# nrf_ha_sensor_USB.net
KiCad netlist of a schematic drawn in Altium Designer
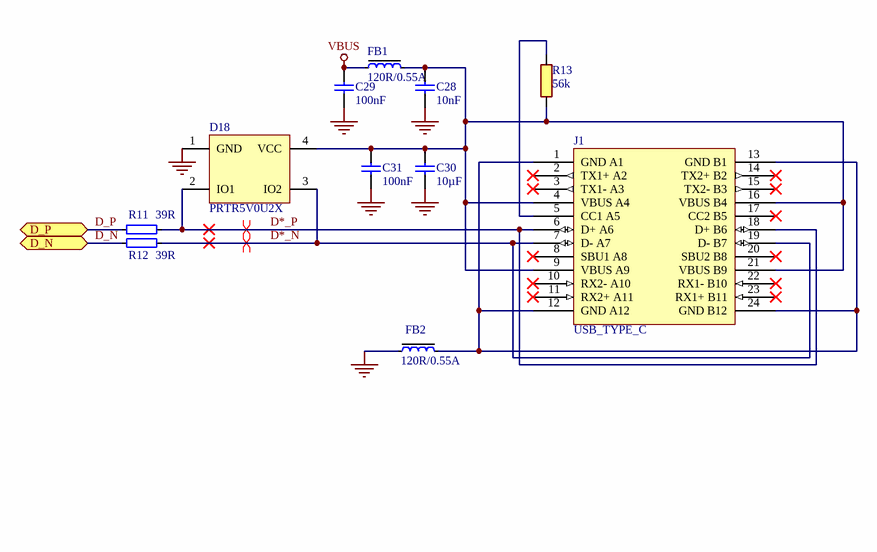
[diagram p0: nrf_ha_sensor_USB.SchDoc]

(export (version "E")
  (design (tool "Eeschema 10.0.6"))
  (components
    (comp (ref "C28")
      (value "10nF")
      (footprint "CAPC1005X04L")
      (description "Capacitor, X7R, ±10%")
      (fields (field (name "PART NUMBER") "C0402-10n") (field (name "PUBLISHER") "Nordic Semiconductor"))
      (libsource (lib "Nordic Passive DB") (part "CAP"))
    )
    (comp (ref "C29")
      (value "100nF")
      (footprint "CAPC1005X04L")
      (description "Capacitor, X7R, ±10%")
      (fields (field (name "PART NUMBER") "C0402-100n") (field (name "PUBLISHER") "Nordic Semiconductor"))
      (libsource (lib "Nordic Passive DB") (part "CAP"))
    )
    (comp (ref "C30")
      (value "10µF")
      (footprint "CAPC1608X06L")
      (description "Capacitor, X5R, ±20%")
      (fields (field (name "PART NUMBER") "C0603-10µ") (field (name "PUBLISHER") "Nordic Semiconductor"))
      (libsource (lib "Nordic Passive DB") (part "CAP"))
    )
    (comp (ref "C31")
      (value "100nF")
      (footprint "CAPC1005X04L")
      (description "Capacitor, X7R, ±10%")
      (fields (field (name "PART NUMBER") "C0402-100n") (field (name "PUBLISHER") "Nordic Semiconductor"))
      (libsource (lib "Nordic Passive DB") (part "CAP"))
    )
    (comp (ref "D18")
      (value "PRTR5V0U2X")
      (footprint "SOT190P230X110-4L")
      (description "Ultra low capacitance double rail-to-rail ESD protection diode")
      (fields
        (field (name "MANUFACTURER") "NXP")
        (field (name "2ND SOURCE PART NUMBER") "152-4157")
        (field (name "PUBLISHER") "Nordic Semiconductor")
      )
      (libsource (lib "Nordic Discrete DB") (part "PRTR5V0U2X"))
    )
    (comp (ref "FB1")
      (value "120R/0.55A")
      (footprint "INDC1005X04L")
      (description "Ferrite Bead, 120 Ohm @ 100MHz, 500mA, 250 mOhm Max")
      (fields
        (field (name "PART NUMBER") "FB0402-120R@100M-500mA")
        (field (name "MANUFACTURER") "Murata")
        (field (name "PUBLISHER") "Nordic Semiconductor")
      )
      (libsource (lib "Nordic Passive DB") (part "IND_F"))
    )
    (comp (ref "FB2")
      (value "120R/0.55A")
      (footprint "INDC1005X04L")
      (description "Ferrite Bead, 120 Ohm @ 100MHz, 500mA, 250 mOhm Max")
      (fields
        (field (name "PART NUMBER") "FB0402-120R@100M-500mA")
        (field (name "MANUFACTURER") "Murata")
        (field (name "PUBLISHER") "Nordic Semiconductor")
      )
      (libsource (lib "Nordic Passive DB") (part "IND_F"))
    )
    (comp (ref "J1")
      (value "USB_TYPE_C")
      (footprint "USB_TYPE_C_JST")
      (description "TH and SMD")
      (libsource (lib "OVLib_64") (part "USB_TYPE_C"))
    )
    (comp (ref "R11")
      (value "39R")
      (footprint "RESC1005X04L")
      (description "Resistor, ±1%, 0.063W")
      (fields (field (name "PART NUMBER") "R0402-39R") (field (name "PUBLISHER") "Nordic Semiconductor"))
      (libsource (lib "Nordic Passive DB") (part "RES_1"))
    )
    (comp (ref "R12")
      (value "39R")
      (footprint "RESC1005X04L")
      (description "Resistor, ±1%, 0.063W")
      (fields (field (name "PART NUMBER") "R0402-39R") (field (name "PUBLISHER") "Nordic Semiconductor"))
      (libsource (lib "Nordic Passive DB") (part "RES_1"))
    )
    (comp (ref "R13")
      (value "56k")
      (footprint "RESC0402(1005)_L")
      (description "0.1W 1% Thick film resistor")
      (libsource (lib "OVLib_64") (part "Resistor2"))
    )
  )
  (nets
    (net (code "1") (name "/D*_N") (class "Default")
      (node (ref "D18") (pin "3") (pinfunction "IO2_3") (pintype "passive"))
      (node (ref "J1") (pin "19") (pinfunction "D-_B7_19") (pintype "bidirectional"))
      (node (ref "J1") (pin "7") (pinfunction "D-_A7_7") (pintype "bidirectional"))
      (node (ref "R11") (pin "2") (pinfunction "2_2") (pintype "passive"))
    )
    (net (code "2") (name "/D*_P") (class "Default")
      (node (ref "D18") (pin "2") (pinfunction "IO1_2") (pintype "passive"))
      (node (ref "J1") (pin "18") (pinfunction "D+_B6_18") (pintype "bidirectional"))
      (node (ref "J1") (pin "6") (pinfunction "D+_A6_6") (pintype "bidirectional"))
      (node (ref "R12") (pin "2") (pinfunction "2_2") (pintype "passive"))
    )
    (net (code "3") (name "/D_N") (class "Default")
      (node (ref "R11") (pin "1") (pinfunction "1_1") (pintype "passive"))
    )
    (net (code "4") (name "/D_P") (class "Default")
      (node (ref "R12") (pin "1") (pinfunction "1_1") (pintype "passive"))
    )
    (net (code "5") (name "GND") (class "Default")
      (node (ref "C28") (pin "1") (pinfunction "1_1") (pintype "passive"))
      (node (ref "C29") (pin "1") (pinfunction "1_1") (pintype "passive"))
      (node (ref "C30") (pin "1") (pinfunction "1_1") (pintype "passive"))
      (node (ref "C31") (pin "1") (pinfunction "1_1") (pintype "passive"))
      (node (ref "D18") (pin "1") (pinfunction "GND_1") (pintype "passive"))
      (node (ref "FB2") (pin "2") (pinfunction "2_2") (pintype "passive"))
    )
    (net (code "6") (name "Net-(D18-VCC)") (class "Default")
      (node (ref "C28") (pin "2") (pinfunction "2_2") (pintype "passive"))
      (node (ref "C30") (pin "2") (pinfunction "2_2") (pintype "passive"))
      (node (ref "C31") (pin "2") (pinfunction "2_2") (pintype "passive"))
      (node (ref "D18") (pin "4") (pinfunction "VCC_4") (pintype "passive"))
      (node (ref "FB1") (pin "1") (pinfunction "1_1") (pintype "passive"))
      (node (ref "J1") (pin "16") (pinfunction "VBUS_B4_16") (pintype "power_in"))
      (node (ref "J1") (pin "21") (pinfunction "VBUS_B9_21") (pintype "power_in"))
      (node (ref "J1") (pin "4") (pinfunction "VBUS_A4_4") (pintype "power_in"))
      (node (ref "J1") (pin "9") (pinfunction "VBUS_A9_9") (pintype "power_in"))
      (node (ref "R13") (pin "1") (pinfunction "1_1") (pintype "passive"))
    )
    (net (code "7") (name "Net-(J1-CC1_A5)") (class "Default")
      (node (ref "J1") (pin "5") (pinfunction "CC1_A5_5") (pintype "passive"))
      (node (ref "R13") (pin "2") (pinfunction "2_2") (pintype "passive"))
    )
    (net (code "8") (name "Net-(J1-GND_A1)") (class "Default")
      (node (ref "FB2") (pin "1") (pinfunction "1_1") (pintype "passive"))
      (node (ref "J1") (pin "1") (pinfunction "GND_A1_1") (pintype "passive"))
      (node (ref "J1") (pin "12") (pinfunction "GND_A12_12") (pintype "passive"))
      (node (ref "J1") (pin "13") (pinfunction "GND_B1_13") (pintype "passive"))
      (node (ref "J1") (pin "24") (pinfunction "GND_B12_24") (pintype "passive"))
    )
    (net (code "9") (name "VBUS") (class "Default")
      (node (ref "C29") (pin "2") (pinfunction "2_2") (pintype "passive"))
      (node (ref "FB1") (pin "2") (pinfunction "2_2") (pintype "passive"))
    )
    (net (code "10") (name "unconnected-(J1-CC2_B5-Pad17)") (class "Default")
      (node (ref "J1") (pin "17") (pinfunction "CC2_B5_17") (pintype "passive+no_connect"))
    )
    (net (code "11") (name "unconnected-(J1-RX1+_B11-Pad23)") (class "Default")
      (node (ref "J1") (pin "23") (pinfunction "RX1+_B11_23") (pintype "input+no_connect"))
    )
    (net (code "12") (name "unconnected-(J1-RX1-_B10-Pad22)") (class "Default")
      (node (ref "J1") (pin "22") (pinfunction "RX1-_B10_22") (pintype "input+no_connect"))
    )
    (net (code "13") (name "unconnected-(J1-RX2+_A11-Pad11)") (class "Default")
      (node (ref "J1") (pin "11") (pinfunction "RX2+_A11_11") (pintype "input+no_connect"))
    )
    (net (code "14") (name "unconnected-(J1-RX2-_A10-Pad10)") (class "Default")
      (node (ref "J1") (pin "10") (pinfunction "RX2-_A10_10") (pintype "input+no_connect"))
    )
    (net (code "15") (name "unconnected-(J1-SBU1_A8-Pad8)") (class "Default")
      (node (ref "J1") (pin "8") (pinfunction "SBU1_A8_8") (pintype "passive+no_connect"))
    )
    (net (code "16") (name "unconnected-(J1-SBU2_B8-Pad20)") (class "Default")
      (node (ref "J1") (pin "20") (pinfunction "SBU2_B8_20") (pintype "passive+no_connect"))
    )
    (net (code "17") (name "unconnected-(J1-TX1+_A2-Pad2)") (class "Default")
      (node (ref "J1") (pin "2") (pinfunction "TX1+_A2_2") (pintype "output+no_connect"))
    )
    (net (code "18") (name "unconnected-(J1-TX1-_A3-Pad3)") (class "Default")
      (node (ref "J1") (pin "3") (pinfunction "TX1-_A3_3") (pintype "output+no_connect"))
    )
    (net (code "19") (name "unconnected-(J1-TX2+_B2-Pad14)") (class "Default")
      (node (ref "J1") (pin "14") (pinfunction "TX2+_B2_14") (pintype "output+no_connect"))
    )
    (net (code "20") (name "unconnected-(J1-TX2-_B3-Pad15)") (class "Default")
      (node (ref "J1") (pin "15") (pinfunction "TX2-_B3_15") (pintype "output+no_connect"))
    )
  )
)
